# hazard.net
KiCad netlist of a schematic drawn in EAGLE
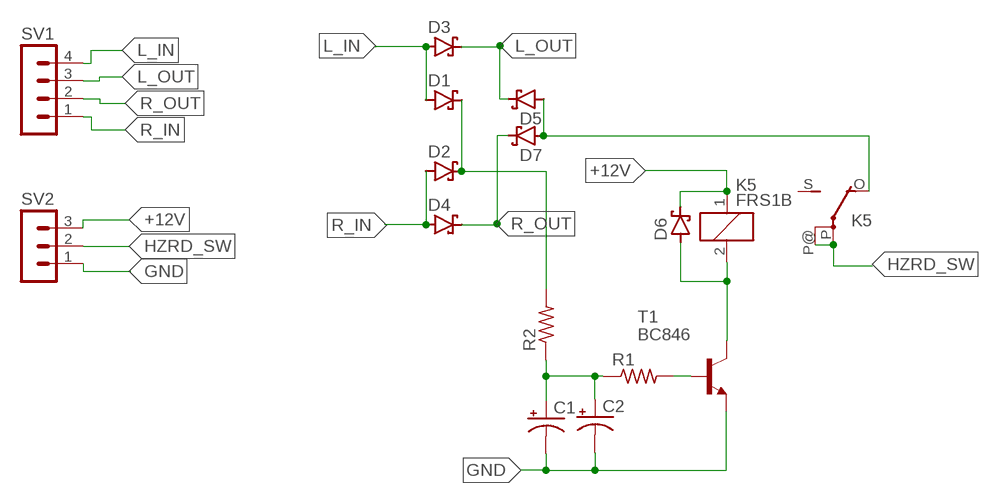
[diagram p0: schematic, sheet 1]

(export (version "E")
  (design (tool "Eeschema 10.0.6"))
  (components
    (comp (ref "C1")
      (value "CPOL-USE1.8-4")
      (footprint "eagle-import:E1,8-4")
      (libsource (lib "eagle-import") (part "CPOL-USE1.8-4"))
    )
    (comp (ref "C2")
      (value "CPOL-USE1.8-4")
      (footprint "eagle-import:E1,8-4")
      (libsource (lib "eagle-import") (part "CPOL-USE1.8-4"))
    )
    (comp (ref "D1")
      (value "SCHOTTKY-DIODESMD")
      (footprint "eagle-import:SMB")
      (libsource (lib "eagle-import") (part "SCHOTTKY-DIODESMD"))
    )
    (comp (ref "D2")
      (value "SCHOTTKY-DIODESMD")
      (footprint "eagle-import:SMB")
      (libsource (lib "eagle-import") (part "SCHOTTKY-DIODESMD"))
    )
    (comp (ref "D3")
      (value "SCHOTTKY-DIODESMD")
      (footprint "eagle-import:SMB")
      (libsource (lib "eagle-import") (part "SCHOTTKY-DIODESMD"))
    )
    (comp (ref "D4")
      (value "SCHOTTKY-DIODESMD")
      (footprint "eagle-import:SMB")
      (libsource (lib "eagle-import") (part "SCHOTTKY-DIODESMD"))
    )
    (comp (ref "D5")
      (value "SCHOTTKY-DIODESMD")
      (footprint "eagle-import:SMB")
      (libsource (lib "eagle-import") (part "SCHOTTKY-DIODESMD"))
    )
    (comp (ref "D6")
      (value "SCHOTTKY-DIODESMD")
      (footprint "eagle-import:SMB")
      (libsource (lib "eagle-import") (part "SCHOTTKY-DIODESMD"))
    )
    (comp (ref "D7")
      (value "SCHOTTKY-DIODESMD")
      (footprint "eagle-import:SMB")
      (libsource (lib "eagle-import") (part "SCHOTTKY-DIODESMD"))
    )
    (comp (ref "K5")
      (value "FRS1B")
      (footprint "eagle-import:FRS1B")
      (libsource (lib "eagle-import") (part "FRS1B"))
    )
    (comp (ref "R1")
      (value "R-US_R0603")
      (footprint "eagle-import:R0603")
      (libsource (lib "eagle-import") (part "R-US_R0603"))
    )
    (comp (ref "R2")
      (value "R-US_R0603")
      (footprint "eagle-import:R0603")
      (libsource (lib "eagle-import") (part "R-US_R0603"))
    )
    (comp (ref "SV1")
      (value "MA04-1")
      (footprint "eagle-import:MA04-1")
      (libsource (lib "eagle-import") (part "MA04-1"))
    )
    (comp (ref "SV2")
      (value "MA03-1")
      (footprint "eagle-import:MA03-1")
      (libsource (lib "eagle-import") (part "MA03-1"))
    )
    (comp (ref "T1")
      (value "BC846")
      (footprint "eagle-import:SOT23")
      (libsource (lib "eagle-import") (part "BC846"))
    )
  )
  (nets
    (net (code "1") (name "+12V") (class "Default")
      (node (ref "D6") (pin "C") (pinfunction "C_C") (pintype "passive"))
      (node (ref "K5") (pin "1") (pinfunction "1_1") (pintype "passive"))
      (node (ref "SV2") (pin "3") (pinfunction "3_3") (pintype "passive"))
    )
    (net (code "2") (name "GND") (class "Default")
      (node (ref "C1") (pin "-") (pinfunction "-_-") (pintype "passive"))
      (node (ref "C2") (pin "-") (pinfunction "-_-") (pintype "passive"))
      (node (ref "SV2") (pin "1") (pinfunction "1_1") (pintype "passive"))
      (node (ref "T1") (pin "2") (pinfunction "E_2") (pintype "passive"))
    )
    (net (code "3") (name "HZRD_SW") (class "Default")
      (node (ref "K5") (pin "P") (pinfunction "P_P") (pintype "passive"))
      (node (ref "K5") (pin "P@") (pinfunction "P_P@") (pintype "passive"))
      (node (ref "SV2") (pin "2") (pinfunction "2_2") (pintype "passive"))
    )
    (net (code "4") (name "L_IN") (class "Default")
      (node (ref "D1") (pin "A") (pinfunction "A_A") (pintype "passive"))
      (node (ref "D3") (pin "A") (pinfunction "A_A") (pintype "passive"))
      (node (ref "SV1") (pin "4") (pinfunction "4_4") (pintype "passive"))
    )
    (net (code "5") (name "L_OUT") (class "Default")
      (node (ref "D3") (pin "C") (pinfunction "C_C") (pintype "passive"))
      (node (ref "D5") (pin "C") (pinfunction "C_C") (pintype "passive"))
      (node (ref "SV1") (pin "3") (pinfunction "3_3") (pintype "passive"))
    )
    (net (code "6") (name "Net-(C1-Pad+)") (class "Default")
      (node (ref "C1") (pin "+") (pinfunction "+_+") (pintype "passive"))
      (node (ref "C2") (pin "+") (pinfunction "+_+") (pintype "passive"))
      (node (ref "R1") (pin "1") (pinfunction "1_1") (pintype "passive"))
      (node (ref "R2") (pin "1") (pinfunction "1_1") (pintype "passive"))
    )
    (net (code "7") (name "Net-(D1-PadC)") (class "Default")
      (node (ref "D1") (pin "C") (pinfunction "C_C") (pintype "passive"))
      (node (ref "D2") (pin "C") (pinfunction "C_C") (pintype "passive"))
      (node (ref "R2") (pin "2") (pinfunction "2_2") (pintype "passive"))
    )
    (net (code "8") (name "Net-(D5-PadA)") (class "Default")
      (node (ref "D5") (pin "A") (pinfunction "A_A") (pintype "passive"))
      (node (ref "D7") (pin "A") (pinfunction "A_A") (pintype "passive"))
      (node (ref "K5") (pin "O") (pinfunction "O_O") (pintype "passive"))
    )
    (net (code "9") (name "Net-(T1-B)") (class "Default")
      (node (ref "R1") (pin "2") (pinfunction "2_2") (pintype "passive"))
      (node (ref "T1") (pin "1") (pinfunction "B_1") (pintype "passive"))
    )
    (net (code "10") (name "Net-(T1-C)") (class "Default")
      (node (ref "D6") (pin "A") (pinfunction "A_A") (pintype "passive"))
      (node (ref "K5") (pin "2") (pinfunction "2_2") (pintype "passive"))
      (node (ref "T1") (pin "3") (pinfunction "C_3") (pintype "passive"))
    )
    (net (code "11") (name "R_IN") (class "Default")
      (node (ref "D2") (pin "A") (pinfunction "A_A") (pintype "passive"))
      (node (ref "D4") (pin "A") (pinfunction "A_A") (pintype "passive"))
      (node (ref "SV1") (pin "1") (pinfunction "1_1") (pintype "passive"))
    )
    (net (code "12") (name "R_OUT") (class "Default")
      (node (ref "D4") (pin "C") (pinfunction "C_C") (pintype "passive"))
      (node (ref "D7") (pin "C") (pinfunction "C_C") (pintype "passive"))
      (node (ref "SV1") (pin "2") (pinfunction "2_2") (pintype "passive"))
    )
    (net (code "13") (name "unconnected-(K5-PadS)") (class "Default")
      (node (ref "K5") (pin "S") (pinfunction "S_S") (pintype "passive"))
    )
  )
)
